# DAC_GainOutputStage5.net
KiCad netlist of a schematic drawn in EAGLE
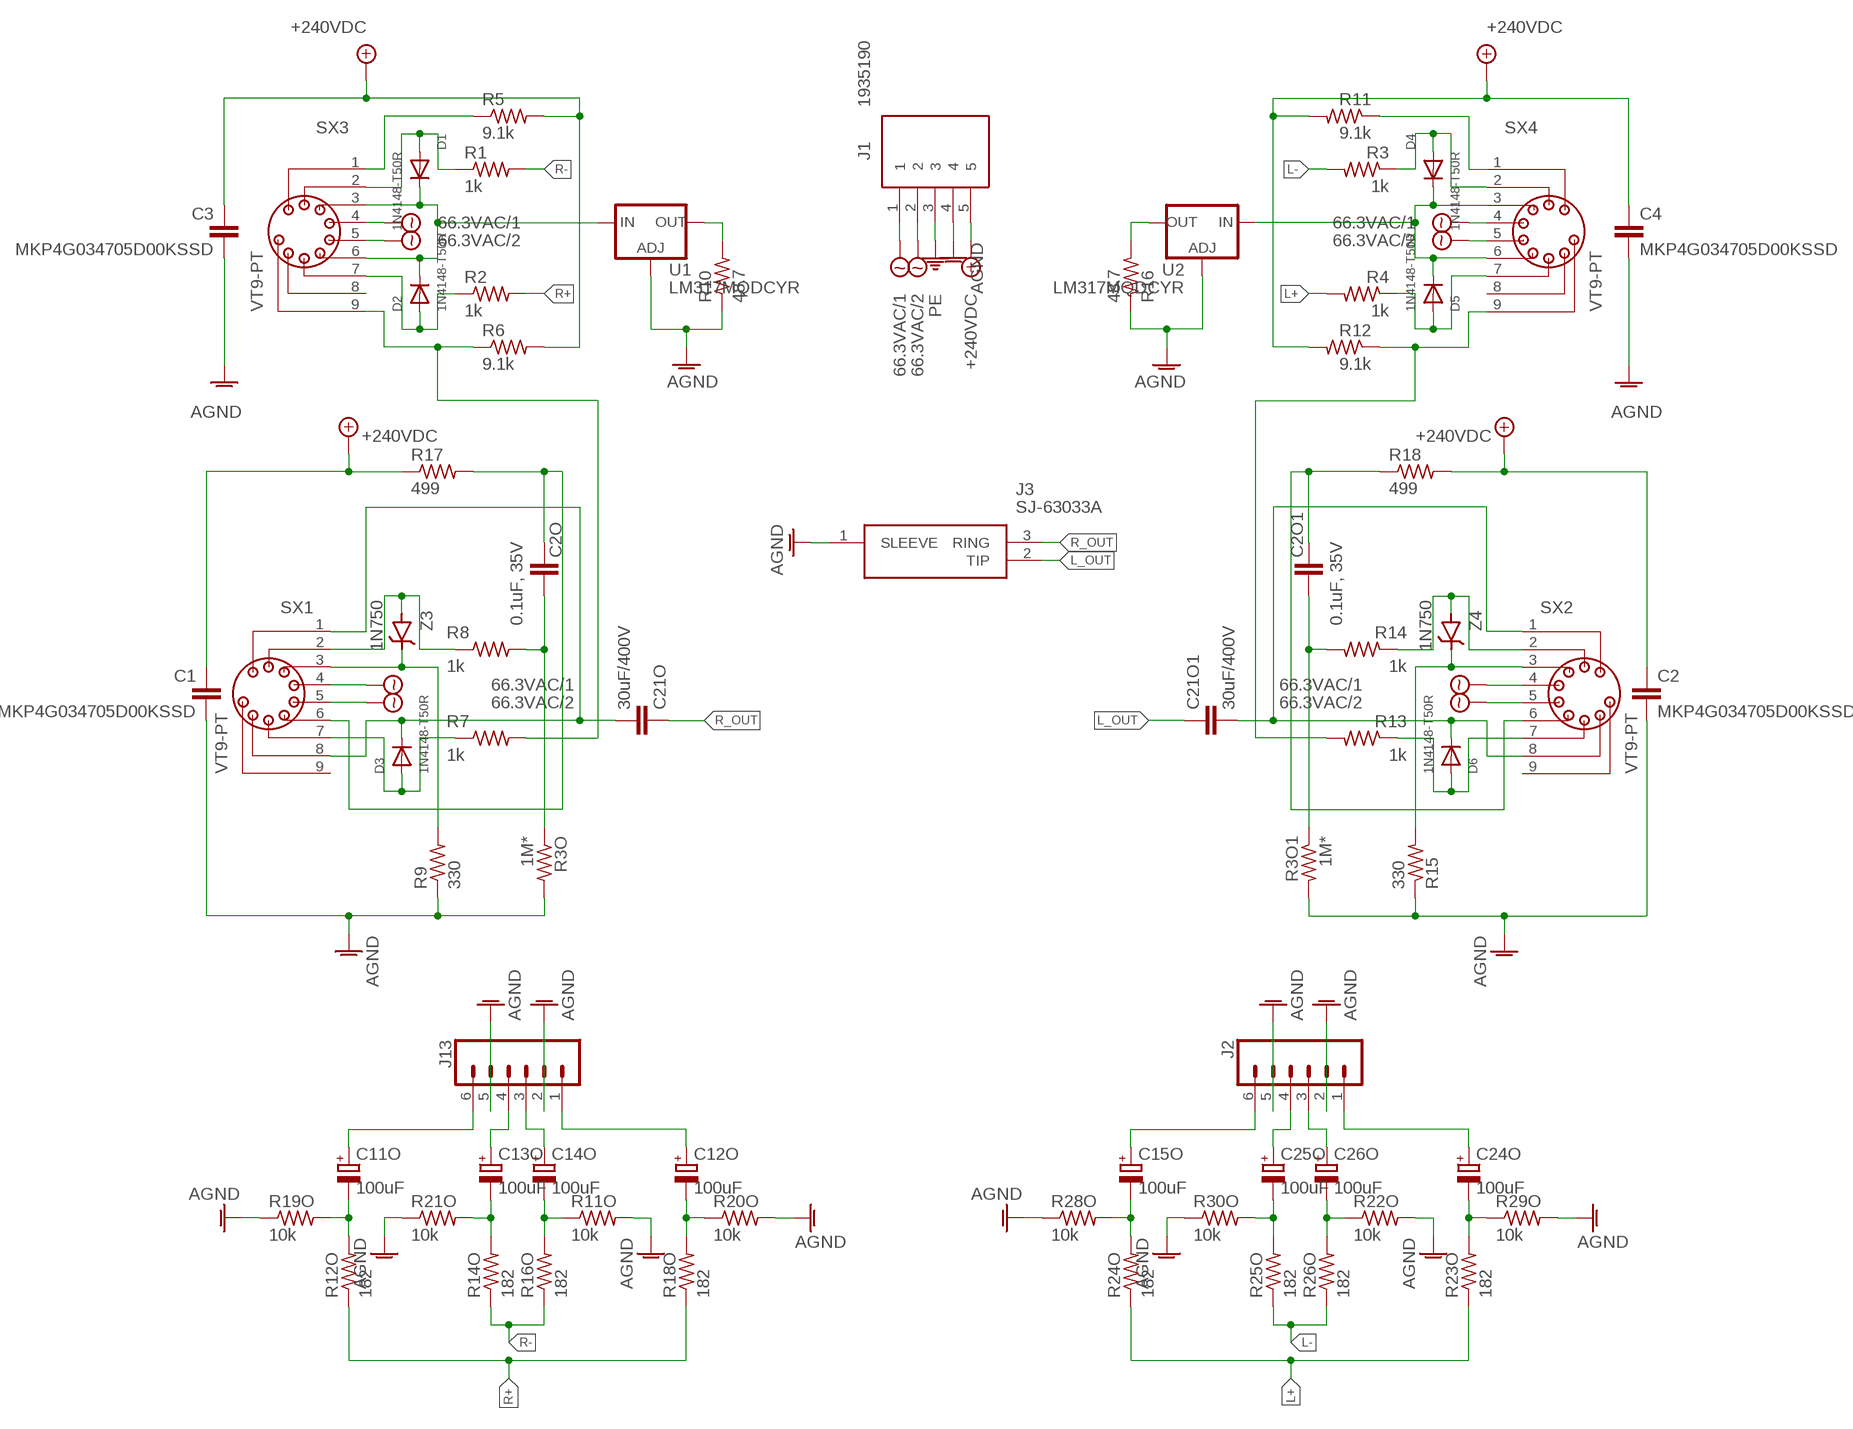
[diagram p0: schematic, sheet 1]

(export (version "E")
  (design (tool "Eeschema 10.0.6"))
  (components
    (comp (ref "C1")
      (value "MKP4G034705D00KSSD")
      (footprint "eagle-import:MKP4G034705D00KSSD")
      (fields (field (name "MOUSER_PART_NUMBER") "505-MKP4G034705DKSSD"))
      (libsource (lib "eagle-import") (part "MKP4G034705D00KSSD"))
    )
    (comp (ref "C2")
      (value "MKP4G034705D00KSSD")
      (footprint "eagle-import:MKP4G034705D00KSSD")
      (fields (field (name "MOUSER_PART_NUMBER") "505-MKP4G034705DKSSD"))
      (libsource (lib "eagle-import") (part "MKP4G034705D00KSSD"))
    )
    (comp (ref "C2O")
      (value "0.1uF, 35V")
      (footprint "eagle-import:MKS4B031002A00JC00")
      (fields
        (field (name "MANUFACTURER_PART_NUMBER") "MKS4B031002A00JC00")
        (field (name "MOUSER_PART_NUMBER") "505-MKS4B0312AJC")
      )
      (libsource (lib "eagle-import") (part "MKS4B031002A00JC00"))
    )
    (comp (ref "C2O1")
      (value "0.1uF, 35V")
      (footprint "eagle-import:MKS4B031002A00JC00")
      (fields
        (field (name "MANUFACTURER_PART_NUMBER") "MKS4B031002A00JC00")
        (field (name "MOUSER_PART_NUMBER") "505-MKS4B0312AJC")
      )
      (libsource (lib "eagle-import") (part "MKS4B031002A00JC00"))
    )
    (comp (ref "C3")
      (value "MKP4G034705D00KSSD")
      (footprint "eagle-import:MKP4G034705D00KSSD")
      (fields (field (name "MOUSER_PART_NUMBER") "505-MKP4G034705DKSSD"))
      (libsource (lib "eagle-import") (part "MKP4G034705D00KSSD"))
    )
    (comp (ref "C4")
      (value "MKP4G034705D00KSSD")
      (footprint "eagle-import:MKP4G034705D00KSSD")
      (fields (field (name "MOUSER_PART_NUMBER") "505-MKP4G034705DKSSD"))
      (libsource (lib "eagle-import") (part "MKP4G034705D00KSSD"))
    )
    (comp (ref "C11O")
      (value "100uF")
      (footprint "eagle-import:CAPPRD350W60D825H1300")
      (fields
        (field (name "ARROW_PART_NUMBER") "UFW1H101MPD1TD")
        (field (name "MOUSER_PART_NUMBER") "647-UFW1H101MPD1TD")
      )
      (libsource (lib "eagle-import") (part "UFW1H101MPD1TD"))
    )
    (comp (ref "C12O")
      (value "100uF")
      (footprint "eagle-import:CAPPRD350W60D825H1300")
      (fields
        (field (name "ARROW_PART_NUMBER") "UFW1H101MPD1TD")
        (field (name "MOUSER_PART_NUMBER") "647-UFW1H101MPD1TD")
      )
      (libsource (lib "eagle-import") (part "UFW1H101MPD1TD"))
    )
    (comp (ref "C13O")
      (value "100uF")
      (footprint "eagle-import:CAPPRD350W60D825H1300")
      (fields
        (field (name "ARROW_PART_NUMBER") "UFW1H101MPD1TD")
        (field (name "MOUSER_PART_NUMBER") "647-UFW1H101MPD1TD")
      )
      (libsource (lib "eagle-import") (part "UFW1H101MPD1TD"))
    )
    (comp (ref "C14O")
      (value "100uF")
      (footprint "eagle-import:CAPPRD350W60D825H1300")
      (fields
        (field (name "ARROW_PART_NUMBER") "UFW1H101MPD1TD")
        (field (name "MOUSER_PART_NUMBER") "647-UFW1H101MPD1TD")
      )
      (libsource (lib "eagle-import") (part "UFW1H101MPD1TD"))
    )
    (comp (ref "C15O")
      (value "100uF")
      (footprint "eagle-import:CAPPRD350W60D825H1300")
      (fields
        (field (name "ARROW_PART_NUMBER") "UFW1H101MPD1TD")
        (field (name "MOUSER_PART_NUMBER") "647-UFW1H101MPD1TD")
      )
      (libsource (lib "eagle-import") (part "UFW1H101MPD1TD"))
    )
    (comp (ref "C21O")
      (value "30uF/400V")
      (footprint "eagle-import:DCP4G053006ID2KSSD")
      (fields
        (field (name "MANUFACTURER_PART_NUMBER") "DCP4G053006ID2KSSD")
        (field (name "MOUSER_PART_NUMBER") "505-DCP4G0536ID2KSSD")
      )
      (libsource (lib "eagle-import") (part "DCP4G053006ID2KSSD"))
    )
    (comp (ref "C21O1")
      (value "30uF/400V")
      (footprint "eagle-import:DCP4G053006ID2KSSD")
      (fields
        (field (name "MANUFACTURER_PART_NUMBER") "DCP4G053006ID2KSSD")
        (field (name "MOUSER_PART_NUMBER") "505-DCP4G0536ID2KSSD")
      )
      (libsource (lib "eagle-import") (part "DCP4G053006ID2KSSD"))
    )
    (comp (ref "C24O")
      (value "100uF")
      (footprint "eagle-import:CAPPRD350W60D825H1300")
      (fields
        (field (name "ARROW_PART_NUMBER") "UFW1H101MPD1TD")
        (field (name "MOUSER_PART_NUMBER") "647-UFW1H101MPD1TD")
      )
      (libsource (lib "eagle-import") (part "UFW1H101MPD1TD"))
    )
    (comp (ref "C25O")
      (value "100uF")
      (footprint "eagle-import:CAPPRD350W60D825H1300")
      (fields
        (field (name "ARROW_PART_NUMBER") "UFW1H101MPD1TD")
        (field (name "MOUSER_PART_NUMBER") "647-UFW1H101MPD1TD")
      )
      (libsource (lib "eagle-import") (part "UFW1H101MPD1TD"))
    )
    (comp (ref "C26O")
      (value "100uF")
      (footprint "eagle-import:CAPPRD350W60D825H1300")
      (fields
        (field (name "ARROW_PART_NUMBER") "UFW1H101MPD1TD")
        (field (name "MOUSER_PART_NUMBER") "647-UFW1H101MPD1TD")
      )
      (libsource (lib "eagle-import") (part "UFW1H101MPD1TD"))
    )
    (comp (ref "D1")
      (value "1N4148-T50R")
      (footprint "eagle-import:DIOAD1068W53L380D172")
      (fields (field (name "MOUSER_PART_NUMBER") "512-1N4148T50R"))
      (libsource (lib "eagle-import") (part "1N4148-T50R"))
    )
    (comp (ref "D2")
      (value "1N4148-T50R")
      (footprint "eagle-import:DIOAD1068W53L380D172")
      (fields (field (name "MOUSER_PART_NUMBER") "512-1N4148T50R"))
      (libsource (lib "eagle-import") (part "1N4148-T50R"))
    )
    (comp (ref "D3")
      (value "1N4148-T50R")
      (footprint "eagle-import:DIOAD1068W53L380D172")
      (fields (field (name "MOUSER_PART_NUMBER") "512-1N4148T50R"))
      (libsource (lib "eagle-import") (part "1N4148-T50R"))
    )
    (comp (ref "D4")
      (value "1N4148-T50R")
      (footprint "eagle-import:DIOAD1068W53L380D172")
      (fields (field (name "MOUSER_PART_NUMBER") "512-1N4148T50R"))
      (libsource (lib "eagle-import") (part "1N4148-T50R"))
    )
    (comp (ref "D5")
      (value "1N4148-T50R")
      (footprint "eagle-import:DIOAD1068W53L380D172")
      (fields (field (name "MOUSER_PART_NUMBER") "512-1N4148T50R"))
      (libsource (lib "eagle-import") (part "1N4148-T50R"))
    )
    (comp (ref "D6")
      (value "1N4148-T50R")
      (footprint "eagle-import:DIOAD1068W53L380D172")
      (fields (field (name "MOUSER_PART_NUMBER") "512-1N4148T50R"))
      (libsource (lib "eagle-import") (part "1N4148-T50R"))
    )
    (comp (ref "J1")
      (value "1935190")
      (footprint "eagle-import:1935190")
      (fields (field (name "MOUSER_PART_NUMBER") "651-1935190"))
      (libsource (lib "eagle-import") (part "1935190"))
    )
    (comp (ref "J2")
      (value "CONN_06SILK_FEMALE_PTH")
      (footprint "eagle-import:1X06")
      (libsource (lib "eagle-import") (part "CONN_06SILK_FEMALE_PTH"))
    )
    (comp (ref "J3")
      (value "SJ-63033A")
      (footprint "eagle-import:SJ63033A")
      (libsource (lib "eagle-import") (part "SJ-63033A"))
    )
    (comp (ref "J13")
      (value "CONN_06SILK_FEMALE_PTH")
      (footprint "eagle-import:1X06")
      (libsource (lib "eagle-import") (part "CONN_06SILK_FEMALE_PTH"))
    )
    (comp (ref "R1")
      (value "1k")
      (footprint "eagle-import:0207_10")
      (fields
        (field (name "MANUFACTURER_PART_NUMBER") "LR1F1K0")
        (field (name "MOUSER_PART_NUMBER") "279-LR1F1K0")
      )
      (libsource (lib "eagle-import") (part "LR1F1K0"))
    )
    (comp (ref "R2")
      (value "1k")
      (footprint "eagle-import:0207_10")
      (fields
        (field (name "MANUFACTURER_PART_NUMBER") "LR1F1K0")
        (field (name "MOUSER_PART_NUMBER") "279-LR1F1K0")
      )
      (libsource (lib "eagle-import") (part "LR1F1K0"))
    )
    (comp (ref "R3")
      (value "1k")
      (footprint "eagle-import:0207_10")
      (fields
        (field (name "MANUFACTURER_PART_NUMBER") "LR1F1K0")
        (field (name "MOUSER_PART_NUMBER") "279-LR1F1K0")
      )
      (libsource (lib "eagle-import") (part "LR1F1K0"))
    )
    (comp (ref "R3O")
      (value "1M*")
      (footprint "eagle-import:0207_10")
      (fields
        (field (name "MANUFACTURER_PART_NUMBER") "LR1F1M0")
        (field (name "MOUSER_PART_NUMBER") "279-LR1F1M0")
      )
      (libsource (lib "eagle-import") (part "LR1F1M0"))
    )
    (comp (ref "R3O1")
      (value "1M*")
      (footprint "eagle-import:0207_10")
      (fields
        (field (name "MANUFACTURER_PART_NUMBER") "LR1F1M0")
        (field (name "MOUSER_PART_NUMBER") "279-LR1F1M0")
      )
      (libsource (lib "eagle-import") (part "LR1F1M0"))
    )
    (comp (ref "R4")
      (value "1k")
      (footprint "eagle-import:0207_10")
      (fields
        (field (name "MANUFACTURER_PART_NUMBER") "LR1F1K0")
        (field (name "MOUSER_PART_NUMBER") "279-LR1F1K0")
      )
      (libsource (lib "eagle-import") (part "LR1F1K0"))
    )
    (comp (ref "R5")
      (value "9.1k")
      (footprint "eagle-import:0411_15")
      (fields
        (field (name "MANUFACTURER_PART_NUMBER") "PR02000209101FA100")
        (field (name "MOUSER_PART_NUMBER") "594-PR02000209101FA1")
      )
      (libsource (lib "eagle-import") (part "PR02000209101FA100"))
    )
    (comp (ref "R6")
      (value "9.1k")
      (footprint "eagle-import:0411_15")
      (fields
        (field (name "MANUFACTURER_PART_NUMBER") "PR02000209101FA100")
        (field (name "MOUSER_PART_NUMBER") "594-PR02000209101FA1")
      )
      (libsource (lib "eagle-import") (part "PR02000209101FA100"))
    )
    (comp (ref "R7")
      (value "1k")
      (footprint "eagle-import:0207_10")
      (fields
        (field (name "MANUFACTURER_PART_NUMBER") "LR1F1K0")
        (field (name "MOUSER_PART_NUMBER") "279-LR1F1K0")
      )
      (libsource (lib "eagle-import") (part "LR1F1K0"))
    )
    (comp (ref "R8")
      (value "1k")
      (footprint "eagle-import:0207_10")
      (fields
        (field (name "MANUFACTURER_PART_NUMBER") "LR1F1K0")
        (field (name "MOUSER_PART_NUMBER") "279-LR1F1K0")
      )
      (libsource (lib "eagle-import") (part "LR1F1K0"))
    )
    (comp (ref "R9")
      (value "330")
      (footprint "eagle-import:0207_10")
      (fields
        (field (name "MANUFACTURER_PART_NUMBER") "LR1F330R")
        (field (name "MOUSER_PART_NUMBER") "279-LR1F330R")
      )
      (libsource (lib "eagle-import") (part "LR1F330R"))
    )
    (comp (ref "R10")
      (value "48.7")
      (footprint "eagle-import:0207_10")
      (fields
        (field (name "MANUFACTURER_PART_NUMBER") "RN55D48R7FB14")
        (field (name "MOUSER_PART_NUMBER") "71-RN55D-F-48.7")
      )
      (libsource (lib "eagle-import") (part "RN55D48R7FB14"))
    )
    (comp (ref "R11")
      (value "9.1k")
      (footprint "eagle-import:0411_15")
      (fields
        (field (name "MANUFACTURER_PART_NUMBER") "PR02000209101FA100")
        (field (name "MOUSER_PART_NUMBER") "594-PR02000209101FA1")
      )
      (libsource (lib "eagle-import") (part "PR02000209101FA100"))
    )
    (comp (ref "R11O")
      (value "10k")
      (footprint "eagle-import:0207_10")
      (fields
        (field (name "MANUFACTURER_PART_NUMBER") "LR1F10K")
        (field (name "MOUSER_PART_NUMBER") "279-LR1F10K")
      )
      (libsource (lib "eagle-import") (part "LR1F10K"))
    )
    (comp (ref "R12")
      (value "9.1k")
      (footprint "eagle-import:0411_15")
      (fields
        (field (name "MANUFACTURER_PART_NUMBER") "PR02000209101FA100")
        (field (name "MOUSER_PART_NUMBER") "594-PR02000209101FA1")
      )
      (libsource (lib "eagle-import") (part "PR02000209101FA100"))
    )
    (comp (ref "R12O")
      (value "182")
      (footprint "eagle-import:0207_10")
      (fields
        (field (name "MANUFACTURER") "Yageo")
        (field (name "MANUFACTURER_PART_NUMBER") "MF0207FTE52-182R")
        (field (name "MOUSER_PART_NUMBER") "603-MF0207FTE52-182R")
      )
      (libsource (lib "eagle-import") (part "MF0207FTE52-182R"))
    )
    (comp (ref "R13")
      (value "1k")
      (footprint "eagle-import:0207_10")
      (fields
        (field (name "MANUFACTURER_PART_NUMBER") "LR1F1K0")
        (field (name "MOUSER_PART_NUMBER") "279-LR1F1K0")
      )
      (libsource (lib "eagle-import") (part "LR1F1K0"))
    )
    (comp (ref "R14")
      (value "1k")
      (footprint "eagle-import:0207_10")
      (fields
        (field (name "MANUFACTURER_PART_NUMBER") "LR1F1K0")
        (field (name "MOUSER_PART_NUMBER") "279-LR1F1K0")
      )
      (libsource (lib "eagle-import") (part "LR1F1K0"))
    )
    (comp (ref "R14O")
      (value "182")
      (footprint "eagle-import:0207_10")
      (fields
        (field (name "MANUFACTURER") "Yageo")
        (field (name "MANUFACTURER_PART_NUMBER") "MF0207FTE52-182R")
        (field (name "MOUSER_PART_NUMBER") "603-MF0207FTE52-182R")
      )
      (libsource (lib "eagle-import") (part "MF0207FTE52-182R"))
    )
    (comp (ref "R15")
      (value "330")
      (footprint "eagle-import:0207_10")
      (fields
        (field (name "MANUFACTURER_PART_NUMBER") "LR1F330R")
        (field (name "MOUSER_PART_NUMBER") "279-LR1F330R")
      )
      (libsource (lib "eagle-import") (part "LR1F330R"))
    )
    (comp (ref "R16")
      (value "48.7")
      (footprint "eagle-import:0207_10")
      (fields
        (field (name "MANUFACTURER_PART_NUMBER") "RN55D48R7FB14")
        (field (name "MOUSER_PART_NUMBER") "71-RN55D-F-48.7")
      )
      (libsource (lib "eagle-import") (part "RN55D48R7FB14"))
    )
    (comp (ref "R16O")
      (value "182")
      (footprint "eagle-import:0207_10")
      (fields
        (field (name "MANUFACTURER") "Yageo")
        (field (name "MANUFACTURER_PART_NUMBER") "MF0207FTE52-182R")
        (field (name "MOUSER_PART_NUMBER") "603-MF0207FTE52-182R")
      )
      (libsource (lib "eagle-import") (part "MF0207FTE52-182R"))
    )
    (comp (ref "R17")
      (value "499")
      (footprint "eagle-import:0411_15")
      (fields
        (field (name "MANUFACTURER_PART_NUMBER") "PR02000204990FA100")
        (field (name "MOUSER_PART_NUMBER") "594-PR02000204990FA1")
      )
      (libsource (lib "eagle-import") (part "PR02000204990FA100"))
    )
    (comp (ref "R18")
      (value "499")
      (footprint "eagle-import:0411_15")
      (fields
        (field (name "MANUFACTURER_PART_NUMBER") "PR02000204990FA100")
        (field (name "MOUSER_PART_NUMBER") "594-PR02000204990FA1")
      )
      (libsource (lib "eagle-import") (part "PR02000204990FA100"))
    )
    (comp (ref "R18O")
      (value "182")
      (footprint "eagle-import:0207_10")
      (fields
        (field (name "MANUFACTURER") "Yageo")
        (field (name "MANUFACTURER_PART_NUMBER") "MF0207FTE52-182R")
        (field (name "MOUSER_PART_NUMBER") "603-MF0207FTE52-182R")
      )
      (libsource (lib "eagle-import") (part "MF0207FTE52-182R"))
    )
    (comp (ref "R19O")
      (value "10k")
      (footprint "eagle-import:0207_10")
      (fields
        (field (name "MANUFACTURER_PART_NUMBER") "LR1F10K")
        (field (name "MOUSER_PART_NUMBER") "279-LR1F10K")
      )
      (libsource (lib "eagle-import") (part "LR1F10K"))
    )
    (comp (ref "R20O")
      (value "10k")
      (footprint "eagle-import:0207_10")
      (fields
        (field (name "MANUFACTURER_PART_NUMBER") "LR1F10K")
        (field (name "MOUSER_PART_NUMBER") "279-LR1F10K")
      )
      (libsource (lib "eagle-import") (part "LR1F10K"))
    )
    (comp (ref "R21O")
      (value "10k")
      (footprint "eagle-import:0207_10")
      (fields
        (field (name "MANUFACTURER_PART_NUMBER") "LR1F10K")
        (field (name "MOUSER_PART_NUMBER") "279-LR1F10K")
      )
      (libsource (lib "eagle-import") (part "LR1F10K"))
    )
    (comp (ref "R22O")
      (value "10k")
      (footprint "eagle-import:0207_10")
      (fields
        (field (name "MANUFACTURER_PART_NUMBER") "LR1F10K")
        (field (name "MOUSER_PART_NUMBER") "279-LR1F10K")
      )
      (libsource (lib "eagle-import") (part "LR1F10K"))
    )
    (comp (ref "R23O")
      (value "182")
      (footprint "eagle-import:0207_10")
      (fields
        (field (name "MANUFACTURER") "Yageo")
        (field (name "MANUFACTURER_PART_NUMBER") "MF0207FTE52-182R")
        (field (name "MOUSER_PART_NUMBER") "603-MF0207FTE52-182R")
      )
      (libsource (lib "eagle-import") (part "MF0207FTE52-182R"))
    )
    (comp (ref "R24O")
      (value "182")
      (footprint "eagle-import:0207_10")
      (fields
        (field (name "MANUFACTURER") "Yageo")
        (field (name "MANUFACTURER_PART_NUMBER") "MF0207FTE52-182R")
        (field (name "MOUSER_PART_NUMBER") "603-MF0207FTE52-182R")
      )
      (libsource (lib "eagle-import") (part "MF0207FTE52-182R"))
    )
    (comp (ref "R25O")
      (value "182")
      (footprint "eagle-import:0207_10")
      (fields
        (field (name "MANUFACTURER") "Yageo")
        (field (name "MANUFACTURER_PART_NUMBER") "MF0207FTE52-182R")
        (field (name "MOUSER_PART_NUMBER") "603-MF0207FTE52-182R")
      )
      (libsource (lib "eagle-import") (part "MF0207FTE52-182R"))
    )
    (comp (ref "R26O")
      (value "182")
      (footprint "eagle-import:0207_10")
      (fields
        (field (name "MANUFACTURER") "Yageo")
        (field (name "MANUFACTURER_PART_NUMBER") "MF0207FTE52-182R")
        (field (name "MOUSER_PART_NUMBER") "603-MF0207FTE52-182R")
      )
      (libsource (lib "eagle-import") (part "MF0207FTE52-182R"))
    )
    (comp (ref "R28O")
      (value "10k")
      (footprint "eagle-import:0207_10")
      (fields
        (field (name "MANUFACTURER_PART_NUMBER") "LR1F10K")
        (field (name "MOUSER_PART_NUMBER") "279-LR1F10K")
      )
      (libsource (lib "eagle-import") (part "LR1F10K"))
    )
    (comp (ref "R29O")
      (value "10k")
      (footprint "eagle-import:0207_10")
      (fields
        (field (name "MANUFACTURER_PART_NUMBER") "LR1F10K")
        (field (name "MOUSER_PART_NUMBER") "279-LR1F10K")
      )
      (libsource (lib "eagle-import") (part "LR1F10K"))
    )
    (comp (ref "R30O")
      (value "10k")
      (footprint "eagle-import:0207_10")
      (fields
        (field (name "MANUFACTURER_PART_NUMBER") "LR1F10K")
        (field (name "MOUSER_PART_NUMBER") "279-LR1F10K")
      )
      (libsource (lib "eagle-import") (part "LR1F10K"))
    )
    (comp (ref "SX1")
      (value "VT9-PT")
      (footprint "eagle-import:VT9-PT")
      (libsource (lib "eagle-import") (part "VT9-PT"))
    )
    (comp (ref "SX2")
      (value "VT9-PT")
      (footprint "eagle-import:VT9-PT")
      (libsource (lib "eagle-import") (part "VT9-PT"))
    )
    (comp (ref "SX3")
      (value "VT9-PT")
      (footprint "eagle-import:VT9-PT")
      (libsource (lib "eagle-import") (part "VT9-PT"))
    )
    (comp (ref "SX4")
      (value "VT9-PT")
      (footprint "eagle-import:VT9-PT")
      (libsource (lib "eagle-import") (part "VT9-PT"))
    )
    (comp (ref "U1")
      (value "LM317MQDCYR")
      (footprint "eagle-import:SOT230P700X180-4N")
      (fields (field (name "MOUSER_PART_NUMBER") "595-LM317MQDCYR"))
      (libsource (lib "eagle-import") (part "LM317MQDCYR"))
    )
    (comp (ref "U2")
      (value "LM317MQDCYR")
      (footprint "eagle-import:SOT230P700X180-4N")
      (fields (field (name "MOUSER_PART_NUMBER") "595-LM317MQDCYR"))
      (libsource (lib "eagle-import") (part "LM317MQDCYR"))
    )
    (comp (ref "Z3")
      (value "1N750")
      (footprint "eagle-import:DIOAD1256W56L444D203")
      (fields (field (name "MOUSER_PART_NUMBER") "494-1N750(DO-35)"))
      (libsource (lib "eagle-import") (part "1N750"))
    )
    (comp (ref "Z4")
      (value "1N750")
      (footprint "eagle-import:DIOAD1256W56L444D203")
      (fields (field (name "MOUSER_PART_NUMBER") "494-1N750(DO-35)"))
      (libsource (lib "eagle-import") (part "1N750"))
    )
  )
  (nets
    (net (code "1") (name "+240VDC") (class "Default")
      (node (ref "C1") (pin "1") (pinfunction "1_1") (pintype "passive"))
      (node (ref "C2") (pin "1") (pinfunction "1_1") (pintype "passive"))
      (node (ref "C3") (pin "1") (pinfunction "1_1") (pintype "passive"))
      (node (ref "C4") (pin "1") (pinfunction "1_1") (pintype "passive"))
      (node (ref "J1") (pin "5") (pinfunction "5_5") (pintype "bidirectional"))
      (node (ref "R11") (pin "2") (pinfunction "2_2") (pintype "passive"))
      (node (ref "R12") (pin "2") (pinfunction "2_2") (pintype "passive"))
      (node (ref "R17") (pin "1") (pinfunction "1_1") (pintype "passive"))
      (node (ref "R18") (pin "2") (pinfunction "2_2") (pintype "passive"))
      (node (ref "R5") (pin "2") (pinfunction "2_2") (pintype "passive"))
      (node (ref "R6") (pin "2") (pinfunction "2_2") (pintype "passive"))
    )
    (net (code "2") (name "66.3VAC{slash}1") (class "Default")
      (node (ref "J1") (pin "1") (pinfunction "1_1") (pintype "bidirectional"))
      (node (ref "SX1") (pin "4") (pinfunction "4_4") (pintype "passive"))
      (node (ref "SX2") (pin "4") (pinfunction "4_4") (pintype "passive"))
      (node (ref "SX3") (pin "4") (pinfunction "4_4") (pintype "passive"))
      (node (ref "SX4") (pin "4") (pinfunction "4_4") (pintype "passive"))
    )
    (net (code "3") (name "66.3VAC{slash}2") (class "Default")
      (node (ref "J1") (pin "2") (pinfunction "2_2") (pintype "bidirectional"))
      (node (ref "SX1") (pin "5") (pinfunction "5_5") (pintype "passive"))
      (node (ref "SX2") (pin "5") (pinfunction "5_5") (pintype "passive"))
      (node (ref "SX3") (pin "5") (pinfunction "5_5") (pintype "passive"))
      (node (ref "SX4") (pin "5") (pinfunction "5_5") (pintype "passive"))
    )
    (net (code "4") (name "AGND") (class "Default")
      (node (ref "C1") (pin "2") (pinfunction "2_2") (pintype "passive"))
      (node (ref "C2") (pin "2") (pinfunction "2_2") (pintype "passive"))
      (node (ref "C3") (pin "2") (pinfunction "2_2") (pintype "passive"))
      (node (ref "C4") (pin "2") (pinfunction "2_2") (pintype "passive"))
      (node (ref "J1") (pin "4") (pinfunction "4_4") (pintype "bidirectional"))
      (node (ref "J13") (pin "2") (pinfunction "2_2") (pintype "passive"))
      (node (ref "J13") (pin "5") (pinfunction "5_5") (pintype "passive"))
      (node (ref "J2") (pin "2") (pinfunction "2_2") (pintype "passive"))
      (node (ref "J2") (pin "5") (pinfunction "5_5") (pintype "passive"))
      (node (ref "J3") (pin "1") (pinfunction "SLEEVE_1") (pintype "bidirectional"))
      (node (ref "R10") (pin "1") (pinfunction "1_1") (pintype "passive"))
      (node (ref "R11O") (pin "2") (pinfunction "2_2") (pintype "passive"))
      (node (ref "R15") (pin "1") (pinfunction "1_1") (pintype "passive"))
      (node (ref "R16") (pin "1") (pinfunction "1_1") (pintype "passive"))
      (node (ref "R19O") (pin "1") (pinfunction "1_1") (pintype "passive"))
      (node (ref "R20O") (pin "2") (pinfunction "2_2") (pintype "passive"))
      (node (ref "R21O") (pin "1") (pinfunction "1_1") (pintype "passive"))
      (node (ref "R22O") (pin "2") (pinfunction "2_2") (pintype "passive"))
      (node (ref "R28O") (pin "1") (pinfunction "1_1") (pintype "passive"))
      (node (ref "R29O") (pin "2") (pinfunction "2_2") (pintype "passive"))
      (node (ref "R30O") (pin "1") (pinfunction "1_1") (pintype "passive"))
      (node (ref "R3O") (pin "2") (pinfunction "2_2") (pintype "passive"))
      (node (ref "R3O1") (pin "2") (pinfunction "2_2") (pintype "passive"))
      (node (ref "R9") (pin "1") (pinfunction "1_1") (pintype "passive"))
      (node (ref "U1") (pin "1") (pinfunction "ADJ_1") (pintype "input"))
      (node (ref "U2") (pin "1") (pinfunction "ADJ_1") (pintype "input"))
    )
    (net (code "5") (name "L+") (class "Default")
      (node (ref "R23O") (pin "1") (pinfunction "1_1") (pintype "passive"))
      (node (ref "R24O") (pin "1") (pinfunction "1_1") (pintype "passive"))
      (node (ref "R4") (pin "2") (pinfunction "2_2") (pintype "passive"))
    )
    (net (code "6") (name "L-") (class "Default")
      (node (ref "R25O") (pin "1") (pinfunction "1_1") (pintype "passive"))
      (node (ref "R26O") (pin "1") (pinfunction "1_1") (pintype "passive"))
      (node (ref "R3") (pin "2") (pinfunction "2_2") (pintype "passive"))
    )
    (net (code "7") (name "L_OUT") (class "Default")
      (node (ref "C21O1") (pin "1") (pinfunction "1_1") (pintype "passive"))
      (node (ref "J3") (pin "2") (pinfunction "TIP_2") (pintype "bidirectional"))
    )
    (net (code "8") (name "Net-(C2O-Pad1)") (class "Default")
      (node (ref "C2O") (pin "1") (pinfunction "1_1") (pintype "passive"))
      (node (ref "R17") (pin "2") (pinfunction "2_2") (pintype "passive"))
      (node (ref "SX1") (pin "6") (pinfunction "6_6") (pintype "passive"))
    )
    (net (code "9") (name "Net-(C2O-Pad2)") (class "Default")
      (node (ref "C2O") (pin "2") (pinfunction "2_2") (pintype "passive"))
      (node (ref "R3O") (pin "1") (pinfunction "1_1") (pintype "passive"))
      (node (ref "R8") (pin "2") (pinfunction "2_2") (pintype "passive"))
    )
    (net (code "10") (name "Net-(C2O1-Pad1)") (class "Default")
      (node (ref "C2O1") (pin "1") (pinfunction "1_1") (pintype "passive"))
      (node (ref "R18") (pin "1") (pinfunction "1_1") (pintype "passive"))
      (node (ref "SX2") (pin "6") (pinfunction "6_6") (pintype "passive"))
    )
    (net (code "11") (name "Net-(C2O1-Pad2)") (class "Default")
      (node (ref "C2O1") (pin "2") (pinfunction "2_2") (pintype "passive"))
      (node (ref "R14") (pin "2") (pinfunction "2_2") (pintype "passive"))
      (node (ref "R3O1") (pin "1") (pinfunction "1_1") (pintype "passive"))
    )
    (net (code "12") (name "Net-(C11O-+)") (class "Default")
      (node (ref "C11O") (pin "1") (pinfunction "+_1") (pintype "passive"))
      (node (ref "J13") (pin "6") (pinfunction "6_6") (pintype "passive"))
    )
    (net (code "13") (name "Net-(C11O--)") (class "Default")
      (node (ref "C11O") (pin "2") (pinfunction "-_2") (pintype "passive"))
      (node (ref "R12O") (pin "2") (pinfunction "2_2") (pintype "passive"))
      (node (ref "R19O") (pin "2") (pinfunction "2_2") (pintype "passive"))
    )
    (net (code "14") (name "Net-(C12O-+)") (class "Default")
      (node (ref "C12O") (pin "1") (pinfunction "+_1") (pintype "passive"))
      (node (ref "J13") (pin "1") (pinfunction "1_1") (pintype "passive"))
    )
    (net (code "15") (name "Net-(C12O--)") (class "Default")
      (node (ref "C12O") (pin "2") (pinfunction "-_2") (pintype "passive"))
      (node (ref "R18O") (pin "2") (pinfunction "2_2") (pintype "passive"))
      (node (ref "R20O") (pin "1") (pinfunction "1_1") (pintype "passive"))
    )
    (net (code "16") (name "Net-(C13O-+)") (class "Default")
      (node (ref "C13O") (pin "1") (pinfunction "+_1") (pintype "passive"))
      (node (ref "J13") (pin "4") (pinfunction "4_4") (pintype "passive"))
    )
    (net (code "17") (name "Net-(C13O--)") (class "Default")
      (node (ref "C13O") (pin "2") (pinfunction "-_2") (pintype "passive"))
      (node (ref "R14O") (pin "2") (pinfunction "2_2") (pintype "passive"))
      (node (ref "R21O") (pin "2") (pinfunction "2_2") (pintype "passive"))
    )
    (net (code "18") (name "Net-(C14O-+)") (class "Default")
      (node (ref "C14O") (pin "1") (pinfunction "+_1") (pintype "passive"))
      (node (ref "J13") (pin "3") (pinfunction "3_3") (pintype "passive"))
    )
    (net (code "19") (name "Net-(C14O--)") (class "Default")
      (node (ref "C14O") (pin "2") (pinfunction "-_2") (pintype "passive"))
      (node (ref "R11O") (pin "1") (pinfunction "1_1") (pintype "passive"))
      (node (ref "R16O") (pin "2") (pinfunction "2_2") (pintype "passive"))
    )
    (net (code "20") (name "Net-(C15O-+)") (class "Default")
      (node (ref "C15O") (pin "1") (pinfunction "+_1") (pintype "passive"))
      (node (ref "J2") (pin "6") (pinfunction "6_6") (pintype "passive"))
    )
    (net (code "21") (name "Net-(C15O--)") (class "Default")
      (node (ref "C15O") (pin "2") (pinfunction "-_2") (pintype "passive"))
      (node (ref "R24O") (pin "2") (pinfunction "2_2") (pintype "passive"))
      (node (ref "R28O") (pin "2") (pinfunction "2_2") (pintype "passive"))
    )
    (net (code "22") (name "Net-(C24O-+)") (class "Default")
      (node (ref "C24O") (pin "1") (pinfunction "+_1") (pintype "passive"))
      (node (ref "J2") (pin "1") (pinfunction "1_1") (pintype "passive"))
    )
    (net (code "23") (name "Net-(C24O--)") (class "Default")
      (node (ref "C24O") (pin "2") (pinfunction "-_2") (pintype "passive"))
      (node (ref "R23O") (pin "2") (pinfunction "2_2") (pintype "passive"))
      (node (ref "R29O") (pin "1") (pinfunction "1_1") (pintype "passive"))
    )
    (net (code "24") (name "Net-(C25O-+)") (class "Default")
      (node (ref "C25O") (pin "1") (pinfunction "+_1") (pintype "passive"))
      (node (ref "J2") (pin "4") (pinfunction "4_4") (pintype "passive"))
    )
    (net (code "25") (name "Net-(C25O--)") (class "Default")
      (node (ref "C25O") (pin "2") (pinfunction "-_2") (pintype "passive"))
      (node (ref "R25O") (pin "2") (pinfunction "2_2") (pintype "passive"))
      (node (ref "R30O") (pin "2") (pinfunction "2_2") (pintype "passive"))
    )
    (net (code "26") (name "Net-(C26O-+)") (class "Default")
      (node (ref "C26O") (pin "1") (pinfunction "+_1") (pintype "passive"))
      (node (ref "J2") (pin "3") (pinfunction "3_3") (pintype "passive"))
    )
    (net (code "27") (name "Net-(C26O--)") (class "Default")
      (node (ref "C26O") (pin "2") (pinfunction "-_2") (pintype "passive"))
      (node (ref "R22O") (pin "1") (pinfunction "1_1") (pintype "passive"))
      (node (ref "R26O") (pin "2") (pinfunction "2_2") (pintype "passive"))
    )
    (net (code "28") (name "Net-(D1-A)") (class "Default")
      (node (ref "D1") (pin "2") (pinfunction "A_2") (pintype "passive"))
      (node (ref "R1") (pin "1") (pinfunction "1_1") (pintype "passive"))
      (node (ref "SX3") (pin "2") (pinfunction "2_2") (pintype "passive"))
    )
    (net (code "29") (name "Net-(D1-C)") (class "Default")
      (node (ref "D1") (pin "1") (pinfunction "C_1") (pintype "passive"))
      (node (ref "D2") (pin "1") (pinfunction "C_1") (pintype "passive"))
      (node (ref "SX3") (pin "3") (pinfunction "3_3") (pintype "passive"))
      (node (ref "SX3") (pin "6") (pinfunction "6_6") (pintype "passive"))
      (node (ref "U1") (pin "3") (pinfunction "IN_3") (pintype "input"))
    )
    (net (code "30") (name "Net-(D2-A)") (class "Default")
      (node (ref "D2") (pin "2") (pinfunction "A_2") (pintype "passive"))
      (node (ref "R2") (pin "1") (pinfunction "1_1") (pintype "passive"))
      (node (ref "SX3") (pin "7") (pinfunction "7_7") (pintype "passive"))
    )
    (net (code "31") (name "Net-(D3-A)") (class "Default")
      (node (ref "D3") (pin "2") (pinfunction "A_2") (pintype "passive"))
      (node (ref "R7") (pin "1") (pinfunction "1_1") (pintype "passive"))
      (node (ref "SX1") (pin "7") (pinfunction "7_7") (pintype "passive"))
    )
    (net (code "32") (name "Net-(D3-C)") (class "Default")
      (node (ref "C21O") (pin "2") (pinfunction "2_2") (pintype "passive"))
      (node (ref "D3") (pin "1") (pinfunction "C_1") (pintype "passive"))
      (node (ref "SX1") (pin "1") (pinfunction "1_1") (pintype "passive"))
      (node (ref "SX1") (pin "8") (pinfunction "8_8") (pintype "passive"))
    )
    (net (code "33") (name "Net-(D4-A)") (class "Default")
      (node (ref "D4") (pin "2") (pinfunction "A_2") (pintype "passive"))
      (node (ref "R3") (pin "1") (pinfunction "1_1") (pintype "passive"))
      (node (ref "SX4") (pin "2") (pinfunction "2_2") (pintype "passive"))
    )
    (net (code "34") (name "Net-(D4-C)") (class "Default")
      (node (ref "D4") (pin "1") (pinfunction "C_1") (pintype "passive"))
      (node (ref "D5") (pin "1") (pinfunction "C_1") (pintype "passive"))
      (node (ref "SX4") (pin "3") (pinfunction "3_3") (pintype "passive"))
      (node (ref "SX4") (pin "6") (pinfunction "6_6") (pintype "passive"))
      (node (ref "U2") (pin "3") (pinfunction "IN_3") (pintype "input"))
    )
    (net (code "35") (name "Net-(D5-A)") (class "Default")
      (node (ref "D5") (pin "2") (pinfunction "A_2") (pintype "passive"))
      (node (ref "R4") (pin "1") (pinfunction "1_1") (pintype "passive"))
      (node (ref "SX4") (pin "7") (pinfunction "7_7") (pintype "passive"))
    )
    (net (code "36") (name "Net-(D6-A)") (class "Default")
      (node (ref "D6") (pin "2") (pinfunction "A_2") (pintype "passive"))
      (node (ref "R13") (pin "1") (pinfunction "1_1") (pintype "passive"))
      (node (ref "SX2") (pin "7") (pinfunction "7_7") (pintype "passive"))
    )
    (net (code "37") (name "Net-(D6-C)") (class "Default")
      (node (ref "C21O1") (pin "2") (pinfunction "2_2") (pintype "passive"))
      (node (ref "D6") (pin "1") (pinfunction "C_1") (pintype "passive"))
      (node (ref "SX2") (pin "1") (pinfunction "1_1") (pintype "passive"))
      (node (ref "SX2") (pin "8") (pinfunction "8_8") (pintype "passive"))
    )
    (net (code "38") (name "Net-(R5-Pad1)") (class "Default")
      (node (ref "R5") (pin "1") (pinfunction "1_1") (pintype "passive"))
      (node (ref "SX3") (pin "1") (pinfunction "1_1") (pintype "passive"))
    )
    (net (code "39") (name "Net-(R6-Pad1)") (class "Default")
      (node (ref "R6") (pin "1") (pinfunction "1_1") (pintype "passive"))
      (node (ref "R7") (pin "2") (pinfunction "2_2") (pintype "passive"))
      (node (ref "SX3") (pin "9") (pinfunction "9_9") (pintype "passive"))
    )
    (net (code "40") (name "Net-(R10-Pad2)") (class "Default")
      (node (ref "R10") (pin "2") (pinfunction "2_2") (pintype "passive"))
      (node (ref "U1") (pin "2") (pinfunction "OUT_2") (pintype "passive"))
      (node (ref "U1") (pin "4") (pinfunction "OUT_4") (pintype "passive"))
    )
    (net (code "41") (name "Net-(R11-Pad1)") (class "Default")
      (node (ref "R11") (pin "1") (pinfunction "1_1") (pintype "passive"))
      (node (ref "SX4") (pin "1") (pinfunction "1_1") (pintype "passive"))
    )
    (net (code "42") (name "Net-(R12-Pad1)") (class "Default")
      (node (ref "R12") (pin "1") (pinfunction "1_1") (pintype "passive"))
      (node (ref "R13") (pin "2") (pinfunction "2_2") (pintype "passive"))
      (node (ref "SX4") (pin "9") (pinfunction "9_9") (pintype "passive"))
    )
    (net (code "43") (name "Net-(R16-Pad2)") (class "Default")
      (node (ref "R16") (pin "2") (pinfunction "2_2") (pintype "passive"))
      (node (ref "U2") (pin "2") (pinfunction "OUT_2") (pintype "passive"))
      (node (ref "U2") (pin "4") (pinfunction "OUT_4") (pintype "passive"))
    )
    (net (code "44") (name "Net-(Z3-A)") (class "Default")
      (node (ref "R8") (pin "1") (pinfunction "1_1") (pintype "passive"))
      (node (ref "SX1") (pin "2") (pinfunction "2_2") (pintype "passive"))
      (node (ref "Z3") (pin "2") (pinfunction "A_2") (pintype "passive"))
    )
    (net (code "45") (name "Net-(Z3-C)") (class "Default")
      (node (ref "R9") (pin "2") (pinfunction "2_2") (pintype "passive"))
      (node (ref "SX1") (pin "3") (pinfunction "3_3") (pintype "passive"))
      (node (ref "Z3") (pin "1") (pinfunction "C_1") (pintype "passive"))
    )
    (net (code "46") (name "Net-(Z4-A)") (class "Default")
      (node (ref "R14") (pin "1") (pinfunction "1_1") (pintype "passive"))
      (node (ref "SX2") (pin "2") (pinfunction "2_2") (pintype "passive"))
      (node (ref "Z4") (pin "2") (pinfunction "A_2") (pintype "passive"))
    )
    (net (code "47") (name "Net-(Z4-C)") (class "Default")
      (node (ref "R15") (pin "2") (pinfunction "2_2") (pintype "passive"))
      (node (ref "SX2") (pin "3") (pinfunction "3_3") (pintype "passive"))
      (node (ref "Z4") (pin "1") (pinfunction "C_1") (pintype "passive"))
    )
    (net (code "48") (name "PE") (class "Default")
      (node (ref "J1") (pin "3") (pinfunction "3_3") (pintype "bidirectional"))
    )
    (net (code "49") (name "R+") (class "Default")
      (node (ref "R12O") (pin "1") (pinfunction "1_1") (pintype "passive"))
      (node (ref "R18O") (pin "1") (pinfunction "1_1") (pintype "passive"))
      (node (ref "R2") (pin "2") (pinfunction "2_2") (pintype "passive"))
    )
    (net (code "50") (name "R-") (class "Default")
      (node (ref "R1") (pin "2") (pinfunction "2_2") (pintype "passive"))
      (node (ref "R14O") (pin "1") (pinfunction "1_1") (pintype "passive"))
      (node (ref "R16O") (pin "1") (pinfunction "1_1") (pintype "passive"))
    )
    (net (code "51") (name "R_OUT") (class "Default")
      (node (ref "C21O") (pin "1") (pinfunction "1_1") (pintype "passive"))
      (node (ref "J3") (pin "3") (pinfunction "RING_3") (pintype "bidirectional"))
    )
    (net (code "52") (name "unconnected-(SX1-Pad9)") (class "Default")
      (node (ref "SX1") (pin "9") (pinfunction "9_9") (pintype "passive"))
    )
    (net (code "53") (name "unconnected-(SX2-Pad9)") (class "Default")
      (node (ref "SX2") (pin "9") (pinfunction "9_9") (pintype "passive"))
    )
    (net (code "54") (name "unconnected-(SX3-Pad8)") (class "Default")
      (node (ref "SX3") (pin "8") (pinfunction "8_8") (pintype "passive"))
    )
    (net (code "55") (name "unconnected-(SX4-Pad8)") (class "Default")
      (node (ref "SX4") (pin "8") (pinfunction "8_8") (pintype "passive"))
    )
  )
)
